# CH32V203G6U6-R0.net
KiCad netlist of a schematic drawn in Altium Designer
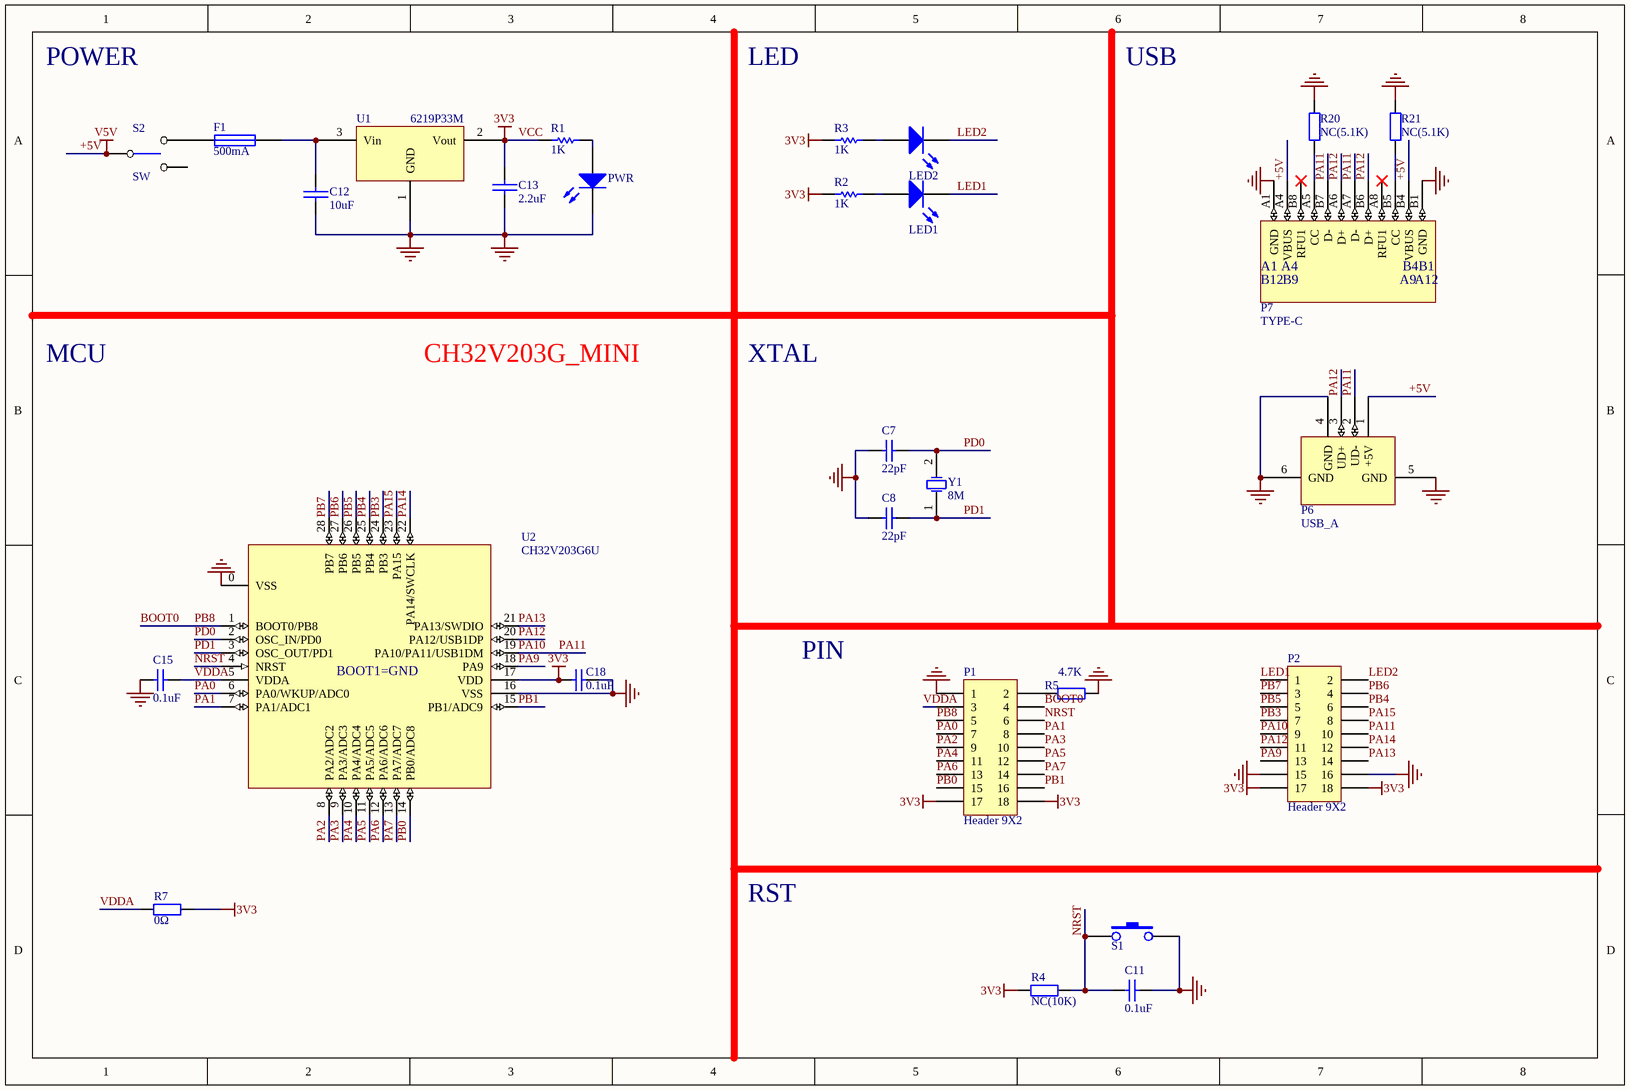
[diagram p0: CH32V203G6U6-R0.SchDoc]

(export (version "E")
  (design (tool "Eeschema 10.0.6"))
  (components
    (comp (ref "C7")
      (value "22pF")
      (footprint "0603_C")
      (description "Capacitor")
      (fields (field (name "PUBLISHER") "Altium Limited"))
      (libsource (lib "*") (part "Cap"))
    )
    (comp (ref "C8")
      (value "22pF")
      (footprint "0603_C")
      (description "Capacitor")
      (fields (field (name "PUBLISHER") "Altium Limited"))
      (libsource (lib "*") (part "Cap"))
    )
    (comp (ref "C11")
      (value "0.1uF")
      (footprint "0603_C")
      (description "Capacitor")
      (fields (field (name "PUBLISHER") "Altium Limited"))
      (libsource (lib "*") (part "Cap"))
    )
    (comp (ref "C12")
      (value "10uF")
      (footprint "3216_C")
      (description "Capacitor")
      (libsource (lib "wch_sch_others") (part "CAP"))
    )
    (comp (ref "C13")
      (value "2.2uF")
      (footprint "0603_C")
      (description "Capacitor")
      (libsource (lib "wch_sch_others") (part "CAP"))
    )
    (comp (ref "C15")
      (value "0.1uF")
      (footprint "0603_C")
      (description "Capacitor")
      (fields (field (name "PUBLISHER") "Altium Limited"))
      (libsource (lib "*") (part "Cap"))
    )
    (comp (ref "C18")
      (value "0.1uF")
      (footprint "0603_C")
      (description "Capacitor")
      (fields (field (name "PUBLISHER") "Altium Limited"))
      (libsource (lib "*") (part "Cap"))
    )
    (comp (ref "F1")
      (value "500mA")
      (footprint "0603")
      (description "Fuse")
      (libsource (lib "*") (part "FUSE1"))
    )
    (comp (ref "LED1")
      (value "LED1   blue")
      (footprint "0603+")
      (description "Typical INFRARED GaAs LED")
      (fields (field (name "PUBLISHER") "Altium Limited"))
      (libsource (lib "*") (part "LED0"))
    )
    (comp (ref "LED2")
      (value "LED2  blue")
      (footprint "0603+")
      (description "Typical INFRARED GaAs LED")
      (fields (field (name "PUBLISHER") "Altium Limited"))
      (libsource (lib "*") (part "LED0"))
    )
    (comp (ref "P1")
      (value "Header 9X2")
      (footprint "IDC18-2.54MM")
      (description "Header, 9-Pin, Dual row")
      (fields (field (name "PUBLISHER") "Altium Limited"))
      (libsource (lib "Miscellaneous Connectors") (part "Header 9X2"))
    )
    (comp (ref "P2")
      (value "Header 9X2")
      (footprint "IDC18-2.54MM")
      (description "Header, 9-Pin, Dual row")
      (fields (field (name "PUBLISHER") "Altium Limited"))
      (libsource (lib "Miscellaneous Connectors") (part "Header 9X2"))
    )
    (comp (ref "P6")
      (value "USB_A")
      (footprint "USBAF")
      (description "USB Port")
      (libsource (lib "*") (part "USB"))
    )
    (comp (ref "P7")
      (value "TYPE-C")
      (footprint "TYPE-C-Receptacle-2.0")
      (libsource (lib "*") (part "TYPE-C1"))
    )
    (comp (ref "PWR")
      (value "POWER  red")
      (footprint "0603+")
      (description "Typical INFRARED GaAs LED")
      (fields (field (name "PUBLISHER") "Altium Limited"))
      (libsource (lib "*") (part "LED0"))
    )
    (comp (ref "R1")
      (value "1K")
      (footprint "0603")
      (description "Semiconductor Resistor")
      (fields (field (name "PUBLISHER") "Altium Limited"))
      (libsource (lib "*") (part "Res Semi"))
    )
    (comp (ref "R2")
      (value "1K")
      (footprint "0603")
      (description "Semiconductor Resistor")
      (fields (field (name "PUBLISHER") "Altium Limited"))
      (libsource (lib "*") (part "Res Semi"))
    )
    (comp (ref "R3")
      (value "1K")
      (footprint "0603")
      (description "Semiconductor Resistor")
      (fields (field (name "PUBLISHER") "Altium Limited"))
      (libsource (lib "*") (part "Res Semi"))
    )
    (comp (ref "R4")
      (value "NC(10K)")
      (footprint "0603")
      (description "Resistor")
      (fields (field (name "PUBLISHER") "Altium Limited"))
      (libsource (lib "*") (part "Res2"))
    )
    (comp (ref "R5")
      (value "4.7K")
      (footprint "0603")
      (description "Resistor")
      (fields (field (name "PUBLISHER") "Altium Limited"))
      (libsource (lib "") (part "Res2_1"))
    )
    (comp (ref "R7")
      (value "0Ω")
      (footprint "0603")
      (description "Resistor")
      (fields (field (name "PUBLISHER") "Altium Limited"))
      (libsource (lib "*") (part "Res2"))
    )
    (comp (ref "R20")
      (value "NC(5.1K)")
      (footprint "0603")
      (description "Resistor")
      (libsource (lib "Miscellaneous Devices") (part "Res2"))
    )
    (comp (ref "R21")
      (value "NC(5.1K)")
      (footprint "0603")
      (description "Resistor")
      (libsource (lib "Miscellaneous Devices") (part "Res2"))
    )
    (comp (ref "S1") (value "RST") (footprint "SMD_6.1x3.65x2.5mm-KEY") (libsource (lib "*") (part "KEY")))
    (comp (ref "S2") (value "SW") (footprint "KEY2") (libsource (lib "*") (part "SW")))
    (comp (ref "U1")
      (value "6219P33M")
      (footprint "SOT-23")
      (libsource (lib "wch_sch_others") (part "6219P33M"))
    )
    (comp (ref "U2")
      (value "CH32V203G6U")
      (footprint "QFN28_4x4")
      (description "RISC-V LMD-MCU, 144MHz, USB FS, CAN, Mul-ADC,OPA")
      (libsource (lib "CHXXX") (part "CH32V203G6U"))
    )
    (comp (ref "Y1")
      (value "8M")
      (footprint "XT_AT49")
      (description "Crystal Oscillator")
      (fields (field (name "PUBLISHER") "Altium Limited"))
      (libsource (lib "*") (part "XTAL"))
    )
  )
  (nets
    (net (code "2") (name "/BOOT0") (class "Default")
      (node (ref "P1") (pin "4") (pinfunction "4_4") (pintype "passive"))
      (node (ref "P1") (pin "5") (pinfunction "5_5") (pintype "passive"))
      (node (ref "U2") (pin "1") (pinfunction "BOOT0/PB8_1") (pintype "bidirectional"))
    )
    (net (code "3") (name "/LED1") (class "Default")
      (node (ref "LED1") (pin "2") (pinfunction "K_2") (pintype "passive"))
      (node (ref "P2") (pin "1") (pinfunction "1_1") (pintype "passive"))
    )
    (net (code "4") (name "/LED2") (class "Default")
      (node (ref "LED2") (pin "2") (pinfunction "K_2") (pintype "passive"))
      (node (ref "P2") (pin "2") (pinfunction "2_2") (pintype "passive"))
    )
    (net (code "5") (name "/NRST") (class "Default")
      (node (ref "C11") (pin "2") (pinfunction "2_2") (pintype "passive"))
      (node (ref "P1") (pin "6") (pinfunction "6_6") (pintype "passive"))
      (node (ref "R4") (pin "1") (pinfunction "1_1") (pintype "passive"))
      (node (ref "S1") (pin "1") (pinfunction "1_1") (pintype "passive"))
      (node (ref "U2") (pin "4") (pinfunction "NRST_4") (pintype "input"))
    )
    (net (code "6") (name "/PA0") (class "Default")
      (node (ref "P1") (pin "7") (pinfunction "7_7") (pintype "passive"))
      (node (ref "U2") (pin "6") (pinfunction "PA0/WKUP/ADC0_6") (pintype "bidirectional"))
    )
    (net (code "7") (name "/PA1") (class "Default")
      (node (ref "P1") (pin "8") (pinfunction "8_8") (pintype "passive"))
      (node (ref "U2") (pin "7") (pinfunction "PA1/ADC1_7") (pintype "bidirectional"))
    )
    (net (code "8") (name "/PA2") (class "Default")
      (node (ref "P1") (pin "9") (pinfunction "9_9") (pintype "passive"))
      (node (ref "U2") (pin "8") (pinfunction "PA2/ADC2_8") (pintype "bidirectional"))
    )
    (net (code "9") (name "/PA3") (class "Default")
      (node (ref "P1") (pin "10") (pinfunction "10_10") (pintype "passive"))
      (node (ref "U2") (pin "9") (pinfunction "PA3/ADC3_9") (pintype "bidirectional"))
    )
    (net (code "10") (name "/PA4") (class "Default")
      (node (ref "P1") (pin "11") (pinfunction "11_11") (pintype "passive"))
      (node (ref "U2") (pin "10") (pinfunction "PA4/ADC4_10") (pintype "bidirectional"))
    )
    (net (code "11") (name "/PA5") (class "Default")
      (node (ref "P1") (pin "12") (pinfunction "12_12") (pintype "passive"))
      (node (ref "U2") (pin "11") (pinfunction "PA5/ADC5_11") (pintype "bidirectional"))
    )
    (net (code "12") (name "/PA6") (class "Default")
      (node (ref "P1") (pin "13") (pinfunction "13_13") (pintype "passive"))
      (node (ref "U2") (pin "12") (pinfunction "PA6/ADC6_12") (pintype "bidirectional"))
    )
    (net (code "13") (name "/PA7") (class "Default")
      (node (ref "P1") (pin "14") (pinfunction "14_14") (pintype "passive"))
      (node (ref "U2") (pin "13") (pinfunction "PA7/ADC7_13") (pintype "bidirectional"))
    )
    (net (code "14") (name "/PA9") (class "Default")
      (node (ref "P2") (pin "13") (pinfunction "13_13") (pintype "passive"))
      (node (ref "U2") (pin "18") (pinfunction "PA9_18") (pintype "bidirectional"))
    )
    (net (code "15") (name "/PA10") (class "Default")
      (node (ref "P2") (pin "10") (pinfunction "10_10") (pintype "passive"))
      (node (ref "P2") (pin "9") (pinfunction "9_9") (pintype "passive"))
      (node (ref "P6") (pin "2") (pinfunction "UD-_2") (pintype "bidirectional"))
      (node (ref "P7") (pin "A7") (pinfunction "D-_A7") (pintype "bidirectional"))
      (node (ref "P7") (pin "B7") (pinfunction "D-_B7") (pintype "bidirectional"))
      (node (ref "U2") (pin "19") (pinfunction "PA10/PA11/USB1DM_19") (pintype "bidirectional"))
    )
    (net (code "16") (name "/PA12") (class "Default")
      (node (ref "P2") (pin "11") (pinfunction "11_11") (pintype "passive"))
      (node (ref "P6") (pin "3") (pinfunction "UD+_3") (pintype "bidirectional"))
      (node (ref "P7") (pin "A6") (pinfunction "D+_A6") (pintype "bidirectional"))
      (node (ref "P7") (pin "B6") (pinfunction "D+_B6") (pintype "bidirectional"))
      (node (ref "U2") (pin "20") (pinfunction "PA12/USB1DP_20") (pintype "bidirectional"))
    )
    (net (code "17") (name "/PA13") (class "Default")
      (node (ref "P2") (pin "14") (pinfunction "14_14") (pintype "passive"))
      (node (ref "U2") (pin "21") (pinfunction "PA13/SWDIO_21") (pintype "bidirectional"))
    )
    (net (code "18") (name "/PA14") (class "Default")
      (node (ref "P2") (pin "12") (pinfunction "12_12") (pintype "passive"))
      (node (ref "U2") (pin "22") (pinfunction "PA14/SWCLK_22") (pintype "bidirectional"))
    )
    (net (code "19") (name "/PA15") (class "Default")
      (node (ref "P2") (pin "8") (pinfunction "8_8") (pintype "passive"))
      (node (ref "U2") (pin "23") (pinfunction "PA15_23") (pintype "bidirectional"))
    )
    (net (code "20") (name "/PB0") (class "Default")
      (node (ref "P1") (pin "15") (pinfunction "15_15") (pintype "passive"))
      (node (ref "U2") (pin "14") (pinfunction "PB0/ADC8_14") (pintype "bidirectional"))
    )
    (net (code "21") (name "/PB1") (class "Default")
      (node (ref "P1") (pin "16") (pinfunction "16_16") (pintype "passive"))
      (node (ref "U2") (pin "15") (pinfunction "PB1/ADC9_15") (pintype "bidirectional"))
    )
    (net (code "22") (name "/PB3") (class "Default")
      (node (ref "P2") (pin "7") (pinfunction "7_7") (pintype "passive"))
      (node (ref "U2") (pin "24") (pinfunction "PB3_24") (pintype "bidirectional"))
    )
    (net (code "23") (name "/PB4") (class "Default")
      (node (ref "P2") (pin "6") (pinfunction "6_6") (pintype "passive"))
      (node (ref "U2") (pin "25") (pinfunction "PB4_25") (pintype "bidirectional"))
    )
    (net (code "24") (name "/PB5") (class "Default")
      (node (ref "P2") (pin "5") (pinfunction "5_5") (pintype "passive"))
      (node (ref "U2") (pin "26") (pinfunction "PB5_26") (pintype "bidirectional"))
    )
    (net (code "25") (name "/PB6") (class "Default")
      (node (ref "P2") (pin "4") (pinfunction "4_4") (pintype "passive"))
      (node (ref "U2") (pin "27") (pinfunction "PB6_27") (pintype "bidirectional"))
    )
    (net (code "26") (name "/PB7") (class "Default")
      (node (ref "P2") (pin "3") (pinfunction "3_3") (pintype "passive"))
      (node (ref "U2") (pin "28") (pinfunction "PB7_28") (pintype "bidirectional"))
    )
    (net (code "27") (name "/PD0") (class "Default")
      (node (ref "C7") (pin "2") (pinfunction "2_2") (pintype "passive"))
      (node (ref "U2") (pin "2") (pinfunction "OSC_IN/PD0_2") (pintype "bidirectional"))
      (node (ref "Y1") (pin "2") (pinfunction "OSC2_2") (pintype "passive"))
    )
    (net (code "28") (name "/PD1") (class "Default")
      (node (ref "C8") (pin "2") (pinfunction "2_2") (pintype "passive"))
      (node (ref "U2") (pin "3") (pinfunction "OSC_OUT/PD1_3") (pintype "bidirectional"))
      (node (ref "Y1") (pin "1") (pinfunction "OSC1_1") (pintype "passive"))
    )
    (net (code "29") (name "/VDDA") (class "Default")
      (node (ref "C15") (pin "1") (pinfunction "1_1") (pintype "passive"))
      (node (ref "P1") (pin "3") (pinfunction "3_3") (pintype "passive"))
      (node (ref "R7") (pin "2") (pinfunction "2_2") (pintype "passive"))
      (node (ref "U2") (pin "5") (pinfunction "VDDA_5") (pintype "power_in"))
    )
    (net (code "30") (name "3V3") (class "Default")
      (node (ref "C13") (pin "2") (pinfunction "2_2") (pintype "passive"))
      (node (ref "C18") (pin "2") (pinfunction "2_2") (pintype "passive"))
      (node (ref "P1") (pin "17") (pinfunction "17_17") (pintype "passive"))
      (node (ref "P1") (pin "18") (pinfunction "18_18") (pintype "passive"))
      (node (ref "P2") (pin "17") (pinfunction "17_17") (pintype "passive"))
      (node (ref "P2") (pin "18") (pinfunction "18_18") (pintype "passive"))
      (node (ref "R1") (pin "2") (pinfunction "2_2") (pintype "passive"))
      (node (ref "R2") (pin "1") (pinfunction "1_1") (pintype "passive"))
      (node (ref "R3") (pin "1") (pinfunction "1_1") (pintype "passive"))
      (node (ref "R4") (pin "2") (pinfunction "2_2") (pintype "passive"))
      (node (ref "R7") (pin "1") (pinfunction "1_1") (pintype "passive"))
      (node (ref "U1") (pin "2") (pinfunction "Vout_2") (pintype "passive"))
      (node (ref "U2") (pin "17") (pinfunction "VDD_17") (pintype "power_in"))
    )
    (net (code "31") (name "GND") (class "Default")
      (node (ref "C11") (pin "1") (pinfunction "1_1") (pintype "passive"))
      (node (ref "C12") (pin "2") (pinfunction "2_2") (pintype "passive"))
      (node (ref "C13") (pin "1") (pinfunction "1_1") (pintype "passive"))
      (node (ref "C15") (pin "2") (pinfunction "2_2") (pintype "passive"))
      (node (ref "C18") (pin "1") (pinfunction "1_1") (pintype "passive"))
      (node (ref "C7") (pin "1") (pinfunction "1_1") (pintype "passive"))
      (node (ref "C8") (pin "1") (pinfunction "1_1") (pintype "passive"))
      (node (ref "P1") (pin "1") (pinfunction "1_1") (pintype "passive"))
      (node (ref "P2") (pin "15") (pinfunction "15_15") (pintype "passive"))
      (node (ref "P2") (pin "16") (pinfunction "16_16") (pintype "passive"))
      (node (ref "P6") (pin "4") (pinfunction "GND_4") (pintype "power_in"))
      (node (ref "P6") (pin "5") (pinfunction "GND_5") (pintype "power_in"))
      (node (ref "P6") (pin "6") (pinfunction "GND_6") (pintype "power_in"))
      (node (ref "P7") (pin "A1") (pinfunction "GND_A1") (pintype "bidirectional"))
      (node (ref "P7") (pin "B1") (pinfunction "GND_B1") (pintype "bidirectional"))
      (node (ref "PWR") (pin "2") (pinfunction "K_2") (pintype "passive"))
      (node (ref "R20") (pin "2") (pinfunction "2_2") (pintype "passive"))
      (node (ref "R21") (pin "2") (pinfunction "2_2") (pintype "passive"))
      (node (ref "R5") (pin "2") (pinfunction "2_2") (pintype "passive"))
      (node (ref "S1") (pin "2") (pinfunction "2_2") (pintype "passive"))
      (node (ref "U1") (pin "1") (pinfunction "GND_1") (pintype "passive"))
      (node (ref "U2") (pin "0") (pinfunction "VSS_0") (pintype "power_in"))
      (node (ref "U2") (pin "16") (pinfunction "VSS_16") (pintype "power_in"))
    )
    (net (code "32") (name "Net-(F1-Pad1)") (class "Default")
      (node (ref "F1") (pin "1") (pinfunction "1_1") (pintype "passive"))
      (node (ref "S2") (pin "3") (pinfunction "3_3") (pintype "passive"))
    )
    (net (code "33") (name "Net-(LED1-A)") (class "Default")
      (node (ref "LED1") (pin "1") (pinfunction "A_1") (pintype "passive"))
      (node (ref "R2") (pin "2") (pinfunction "2_2") (pintype "passive"))
    )
    (net (code "34") (name "Net-(LED2-A)") (class "Default")
      (node (ref "LED2") (pin "1") (pinfunction "A_1") (pintype "passive"))
      (node (ref "R3") (pin "2") (pinfunction "2_2") (pintype "passive"))
    )
    (net (code "35") (name "Net-(P1-Pad2)") (class "Default")
      (node (ref "P1") (pin "2") (pinfunction "2_2") (pintype "passive"))
      (node (ref "R5") (pin "1") (pinfunction "1_1") (pintype "passive"))
    )
    (net (code "36") (name "Net-(P7-CC-PadA5)") (class "Default")
      (node (ref "P7") (pin "A5") (pinfunction "CC_A5") (pintype "bidirectional"))
      (node (ref "R20") (pin "1") (pinfunction "1_1") (pintype "passive"))
    )
    (net (code "37") (name "Net-(P7-CC-PadB5)") (class "Default")
      (node (ref "P7") (pin "B5") (pinfunction "CC_B5") (pintype "bidirectional"))
      (node (ref "R21") (pin "1") (pinfunction "1_1") (pintype "passive"))
    )
    (net (code "38") (name "Net-(PWR-A)") (class "Default")
      (node (ref "PWR") (pin "1") (pinfunction "A_1") (pintype "passive"))
      (node (ref "R1") (pin "1") (pinfunction "1_1") (pintype "passive"))
    )
    (net (code "39") (name "Net-(U1-Vin)") (class "Default")
      (node (ref "C12") (pin "1") (pinfunction "1_1") (pintype "passive"))
      (node (ref "F1") (pin "2") (pinfunction "2_2") (pintype "passive"))
      (node (ref "U1") (pin "3") (pinfunction "Vin_3") (pintype "passive"))
    )
    (net (code "40") (name "V5V") (class "Default")
      (node (ref "P6") (pin "1") (pinfunction "+5V_1") (pintype "power_in"))
      (node (ref "P7") (pin "A4") (pinfunction "VBUS_A4") (pintype "bidirectional"))
      (node (ref "P7") (pin "B4") (pinfunction "VBUS_B4") (pintype "bidirectional"))
      (node (ref "S2") (pin "1") (pinfunction "1_1") (pintype "passive"))
    )
    (net (code "41") (name "unconnected-(P7-RFU1-PadA8)") (class "Default")
      (node (ref "P7") (pin "A8") (pinfunction "RFU1_A8") (pintype "bidirectional+no_connect"))
    )
    (net (code "42") (name "unconnected-(P7-RFU1-PadB8)") (class "Default")
      (node (ref "P7") (pin "B8") (pinfunction "RFU1_B8") (pintype "bidirectional+no_connect"))
    )
    (net (code "43") (name "unconnected-(S2-Pad2)") (class "Default")
      (node (ref "S2") (pin "2") (pinfunction "2_2") (pintype "passive"))
    )
  )
)
